# Output.net
KiCad netlist of a schematic drawn in Altium Designer
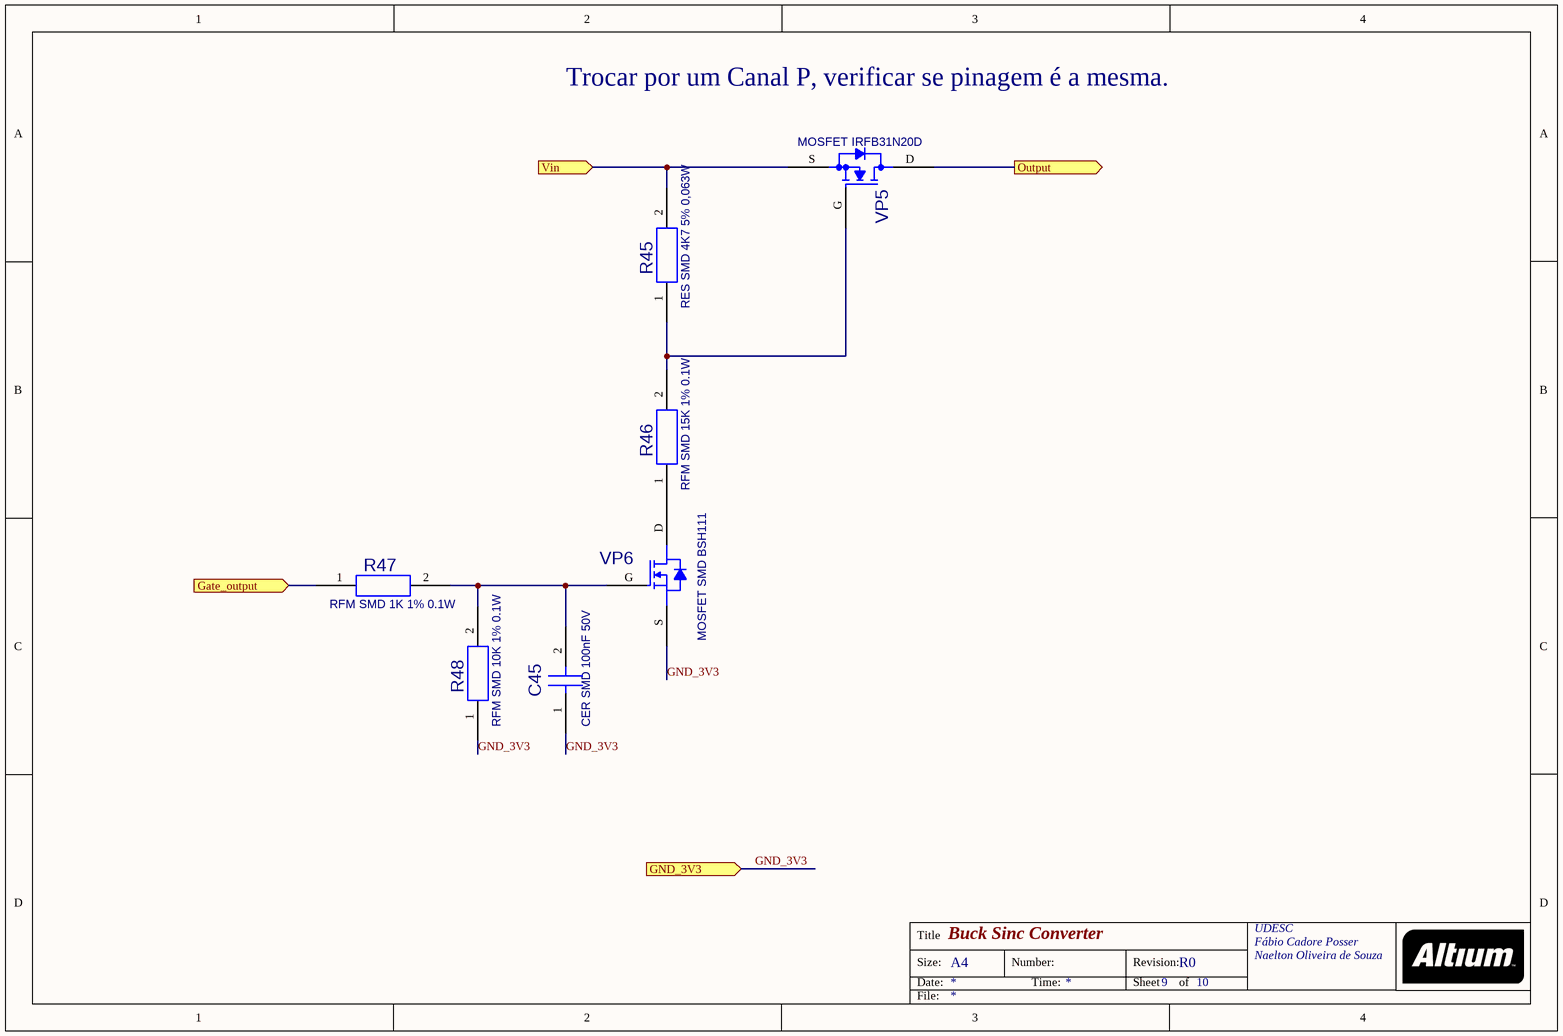
[diagram p0: Output.SchDoc]

(export (version "E")
  (design (tool "Eeschema 10.0.6"))
  (components
    (comp (ref "C45")
      (value "CER SMD 100nF 50V")
      (footprint "C0805_R_V0")
      (fields (field (name "Comment") "10192075"))
      (libsource (lib "Buck_Converter") (part "10192075"))
    )
    (comp (ref "R45")
      (value "RES SMD 4K7 5% 0,063W")
      (footprint "R0805_R_V0")
      (fields (field (name "Comment") "11417855"))
      (libsource (lib "Buck_Converter") (part "10118077"))
    )
    (comp (ref "R46")
      (value "RFM SMD 15K 1% 0.1W")
      (footprint "R0805_R_V0")
      (fields (field (name "Comment") "10118078"))
      (libsource (lib "Buck_Converter") (part "10118077"))
    )
    (comp (ref "R47")
      (value "RFM SMD 1K 1% 0.1W")
      (footprint "R0805_R_V0")
      (fields (field (name "Comment") "10118077"))
      (libsource (lib "Buck_Converter") (part "10118077"))
    )
    (comp (ref "R48")
      (value "RFM SMD 10K 1% 0.1W")
      (footprint "R0805_R_V0")
      (fields (field (name "Comment") "10118076"))
      (libsource (lib "Buck_Converter") (part "10118077"))
    )
    (comp (ref "VP5")
      (value "MOSFET IRFB31N20D")
      (footprint "TO-220AB (Primary)")
      (fields (field (name "Comment") "10190449"))
      (libsource (lib "Buck_Converter") (part "10190449"))
    )
    (comp (ref "VP6")
      (value "MOSFET SMD BSH111")
      (footprint "MOS_SOT23A")
      (fields (field (name "Comment") "11110327"))
      (libsource (lib "Buck_Converter") (part "11110327"))
    )
  )
  (nets
    (net (code "1") (name "/GND_3V3") (class "Default")
      (node (ref "C45") (pin "1") (pinfunction "1_1") (pintype "passive"))
      (node (ref "R48") (pin "1") (pinfunction "1_1") (pintype "passive"))
      (node (ref "VP6") (pin "S") (pinfunction "S_S") (pintype "passive"))
    )
    (net (code "2") (name "/Gate_output") (class "Default")
      (node (ref "R47") (pin "1") (pinfunction "1_1") (pintype "passive"))
    )
    (net (code "3") (name "/Output") (class "Default")
      (node (ref "VP5") (pin "D") (pinfunction "2_D") (pintype "passive"))
    )
    (net (code "4") (name "/Vin") (class "Default")
      (node (ref "R45") (pin "2") (pinfunction "2_2") (pintype "passive"))
      (node (ref "VP5") (pin "S") (pinfunction "3_S") (pintype "passive"))
    )
    (net (code "5") (name "Net-(C45-Pad2)") (class "Default")
      (node (ref "C45") (pin "2") (pinfunction "2_2") (pintype "passive"))
      (node (ref "R47") (pin "2") (pinfunction "2_2") (pintype "passive"))
      (node (ref "R48") (pin "2") (pinfunction "2_2") (pintype "passive"))
      (node (ref "VP6") (pin "G") (pinfunction "G_G") (pintype "passive"))
    )
    (net (code "6") (name "Net-(R46-Pad1)") (class "Default")
      (node (ref "R46") (pin "1") (pinfunction "1_1") (pintype "passive"))
      (node (ref "VP6") (pin "D") (pinfunction "D_D") (pintype "passive"))
    )
    (net (code "7") (name "Net-(VP5-1)") (class "Default")
      (node (ref "R45") (pin "1") (pinfunction "1_1") (pintype "passive"))
      (node (ref "R46") (pin "2") (pinfunction "2_2") (pintype "passive"))
      (node (ref "VP5") (pin "G") (pinfunction "1_G") (pintype "passive"))
    )
  )
)
